# Solenoid_5.net
KiCad netlist of a schematic drawn in EAGLE
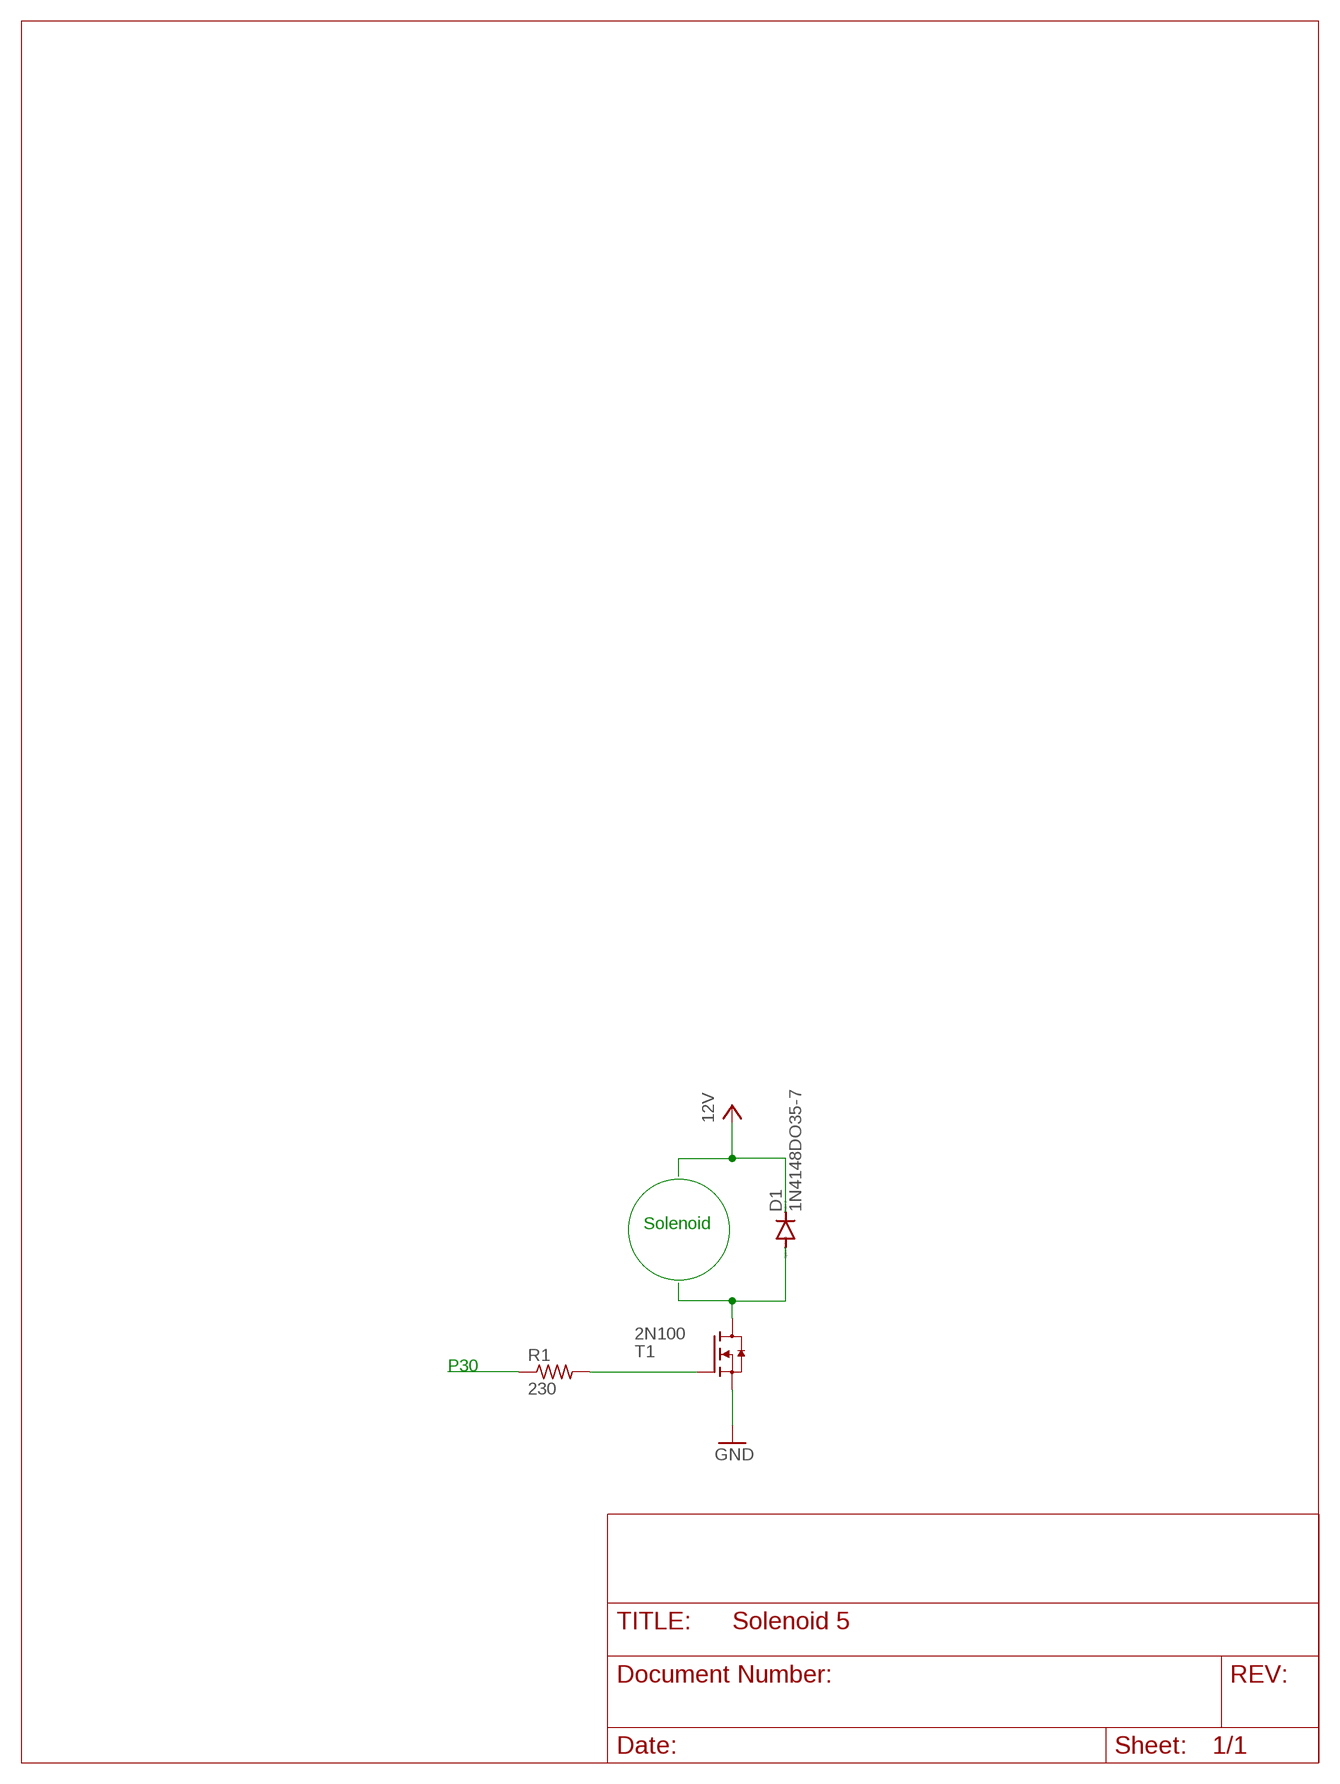
[diagram p0: schematic, sheet 1]

(export (version "E")
  (design (tool "Eeschema 10.0.6"))
  (components
    (comp (ref "D1")
      (value "1N4148DO35-7")
      (footprint "eagle-import:DO35-7")
      (libsource (lib "eagle-import") (part "1N4148DO35-7"))
    )
    (comp (ref "R1")
      (value "230")
      (footprint "eagle-import:0204_7")
      (libsource (lib "eagle-import") (part "R-US_0204/7"))
    )
    (comp (ref "T1")
      (value "2N100")
      (footprint "eagle-import:PG-TO263-7-3")
      (libsource (lib "eagle-import") (part "IPB180N06S4-H1"))
    )
  )
  (nets
    (net (code "1") (name "12V") (class "Default")
      (node (ref "D1") (pin "C") (pinfunction "C_C") (pintype "passive"))
    )
    (net (code "2") (name "GND") (class "Default")
      (node (ref "T1") (pin "2") (pinfunction "S_2") (pintype "passive"))
      (node (ref "T1") (pin "3") (pinfunction "S_3") (pintype "passive"))
      (node (ref "T1") (pin "5") (pinfunction "S_5") (pintype "passive"))
      (node (ref "T1") (pin "6") (pinfunction "S_6") (pintype "passive"))
      (node (ref "T1") (pin "7") (pinfunction "S_7") (pintype "passive"))
    )
    (net (code "3") (name "Net-(T1-D)") (class "Default")
      (node (ref "D1") (pin "A") (pinfunction "A_A") (pintype "passive"))
      (node (ref "T1") (pin "8") (pinfunction "D_8") (pintype "passive"))
    )
    (net (code "4") (name "Net-(T1-G)") (class "Default")
      (node (ref "R1") (pin "2") (pinfunction "2_2") (pintype "passive"))
      (node (ref "T1") (pin "1") (pinfunction "G_1") (pintype "passive"))
    )
    (net (code "5") (name "unconnected-(R1-Pad1)") (class "Default")
      (node (ref "R1") (pin "1") (pinfunction "1_1") (pintype "passive"))
    )
  )
)
